# Power_Supply.net
KiCad netlist of a schematic drawn in Altium Designer
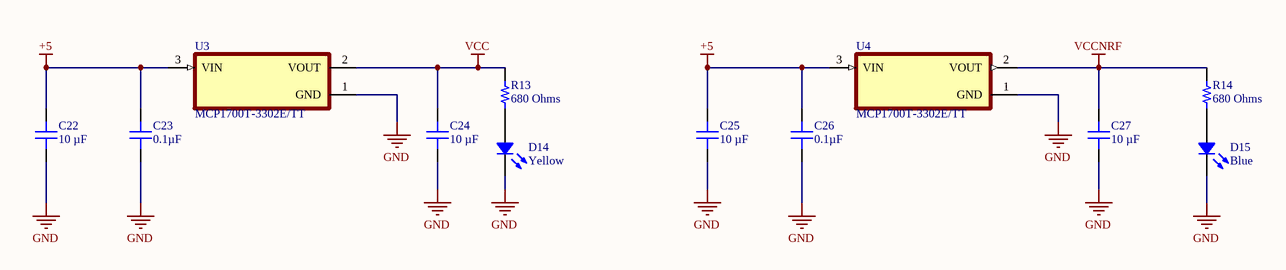
[diagram p0: Power_Supply.SchDoc]

(export (version "E")
  (design (tool "Eeschema 10.0.6"))
  (components
    (comp (ref "C22")
      (value "10 µF")
      (footprint "CAP 0603_1608")
      (description "CAP CER 10UF 6.3V X6S 0603")
      (fields (field (name "PART NUMBER") "KGM15CS60J106MT") (field (name "MANUFACTURER") "KYOCERA AVX"))
      (libsource (lib "Celestial Altium Library - altium_library") (part "Capacitor"))
    )
    (comp (ref "C23")
      (value "0.1µF")
      (footprint "CAP 0603_1608")
      (description "CAP CER 0.1UF 16V X7R 0603")
      (fields (field (name "PART NUMBER") "0603YC104K4T4A") (field (name "MANUFACTURER") "AVX Corporation"))
      (libsource (lib "Celestial Altium Library - altium_library") (part "Capacitor"))
    )
    (comp (ref "C24")
      (value "10 µF")
      (footprint "CAP 0603_1608")
      (description "CAP CER 10UF 6.3V X6S 0603")
      (fields (field (name "PART NUMBER") "KGM15CS60J106MT") (field (name "MANUFACTURER") "KYOCERA AVX"))
      (libsource (lib "Celestial Altium Library - altium_library") (part "Capacitor"))
    )
    (comp (ref "C25")
      (value "10 µF")
      (footprint "CAP 0603_1608")
      (description "CAP CER 10UF 6.3V X6S 0603")
      (fields (field (name "PART NUMBER") "KGM15CS60J106MT") (field (name "MANUFACTURER") "KYOCERA AVX"))
      (libsource (lib "Celestial Altium Library - altium_library") (part "Capacitor"))
    )
    (comp (ref "C26")
      (value "0.1µF")
      (footprint "CAP 0603_1608")
      (description "CAP CER 0.1UF 16V X7R 0603")
      (fields (field (name "PART NUMBER") "0603YC104K4T4A") (field (name "MANUFACTURER") "AVX Corporation"))
      (libsource (lib "Celestial Altium Library - altium_library") (part "Capacitor"))
    )
    (comp (ref "C27")
      (value "10 µF")
      (footprint "CAP 0603_1608")
      (description "CAP CER 10UF 6.3V X6S 0603")
      (fields (field (name "PART NUMBER") "KGM15CS60J106MT") (field (name "MANUFACTURER") "KYOCERA AVX"))
      (libsource (lib "Celestial Altium Library - altium_library") (part "Capacitor"))
    )
    (comp (ref "D14")
      (value "Yellow")
      (footprint "LED 0603_1608 YELLOW")
      (description "LED YELLOW DIFFUSED 1608 SMD")
      (fields (field (name "PART NUMBER") "SML-D15YWT86") (field (name "MANUFACTURER") "Rohm Semiconductor"))
      (libsource (lib "Celestial Altium Library - altium_library") (part "LED"))
    )
    (comp (ref "D15")
      (value "Blue")
      (footprint "LED 0603_1608 BLUE")
      (description "LED BLUE DIFFUSED 0603 SMD")
      (fields
        (field (name "PART NUMBER") "LB Q39G-L2OO-35-1")
        (field (name "MANUFACTURER") "OSRAM Opto Semiconductors Inc.")
      )
      (libsource (lib "Celestial Altium Library - altium_library") (part "LED"))
    )
    (comp (ref "R13")
      (value "680 Ohms")
      (footprint "RES 0603_1608")
      (description "RES SMD 680 OHM 1% 1/10W 0603")
      (fields (field (name "PART NUMBER") "CRCW0603680RFKEA") (field (name "MANUFACTURER") "Vishay Dale"))
      (libsource (lib "Celestial Altium Library - altium_library") (part "Resistor"))
    )
    (comp (ref "R14")
      (value "680 Ohms")
      (footprint "RES 0603_1608")
      (description "RES SMD 680 OHM 1% 1/10W 0603")
      (fields (field (name "PART NUMBER") "CRCW0603680RFKEA") (field (name "MANUFACTURER") "Vishay Dale"))
      (libsource (lib "Celestial Altium Library - altium_library") (part "Resistor"))
    )
    (comp (ref "U3")
      (value "MCP1700T-3302E/TT")
      (footprint "SOT95P237X112-3N")
      (description "Linear Voltage Regulator IC 1 Output 250mA SOT-23-3")
      (fields (field (name "MF") "Microchip"))
      (libsource (lib "MCP1700T-3302E_TT") (part "MCP1700T-3302E/TT"))
    )
    (comp (ref "U4")
      (value "MCP1700T-3302E/TT")
      (footprint "SOT95P237X112-3N")
      (description "Linear Voltage Regulator IC 1 Output 250mA SOT-23-3")
      (fields (field (name "MF") "Microchip"))
      (libsource (lib "MCP1700T-3302E_TT") (part "MCP1700T-3302E/TT"))
    )
  )
  (nets
    (net (code "1") (name "+5") (class "Default")
      (node (ref "C22") (pin "2") (pinfunction "2_2") (pintype "passive"))
      (node (ref "C23") (pin "2") (pinfunction "2_2") (pintype "passive"))
      (node (ref "C25") (pin "2") (pinfunction "2_2") (pintype "passive"))
      (node (ref "C26") (pin "2") (pinfunction "2_2") (pintype "passive"))
      (node (ref "U3") (pin "3") (pinfunction "VIN_3") (pintype "input"))
      (node (ref "U4") (pin "3") (pinfunction "VIN_3") (pintype "input"))
    )
    (net (code "2") (name "GND") (class "Default")
      (node (ref "C22") (pin "1") (pinfunction "1_1") (pintype "passive"))
      (node (ref "C23") (pin "1") (pinfunction "1_1") (pintype "passive"))
      (node (ref "C24") (pin "1") (pinfunction "1_1") (pintype "passive"))
      (node (ref "C25") (pin "1") (pinfunction "1_1") (pintype "passive"))
      (node (ref "C26") (pin "1") (pinfunction "1_1") (pintype "passive"))
      (node (ref "C27") (pin "1") (pinfunction "1_1") (pintype "passive"))
      (node (ref "D14") (pin "2") (pinfunction "2_2") (pintype "passive"))
      (node (ref "D15") (pin "2") (pinfunction "2_2") (pintype "passive"))
      (node (ref "U3") (pin "1") (pinfunction "GND_1") (pintype "power_in"))
      (node (ref "U4") (pin "1") (pinfunction "GND_1") (pintype "power_in"))
    )
    (net (code "3") (name "Net-(D14-Pad1)") (class "Default")
      (node (ref "D14") (pin "1") (pinfunction "1_1") (pintype "passive"))
      (node (ref "R13") (pin "1") (pinfunction "1_1") (pintype "passive"))
    )
    (net (code "4") (name "Net-(D15-Pad1)") (class "Default")
      (node (ref "D15") (pin "1") (pinfunction "1_1") (pintype "passive"))
      (node (ref "R14") (pin "1") (pinfunction "1_1") (pintype "passive"))
    )
    (net (code "5") (name "VCC") (class "Default")
      (node (ref "C24") (pin "2") (pinfunction "2_2") (pintype "passive"))
      (node (ref "R13") (pin "2") (pinfunction "2_2") (pintype "passive"))
      (node (ref "U3") (pin "2") (pinfunction "VOUT_2") (pintype "power_in"))
    )
    (net (code "6") (name "VCCNRF") (class "Default")
      (node (ref "C27") (pin "2") (pinfunction "2_2") (pintype "passive"))
      (node (ref "R14") (pin "2") (pinfunction "2_2") (pintype "passive"))
      (node (ref "U4") (pin "2") (pinfunction "VOUT_2") (pintype "power_in"))
    )
  )
)
